# main.net
KiCad netlist of a schematic drawn in EAGLE
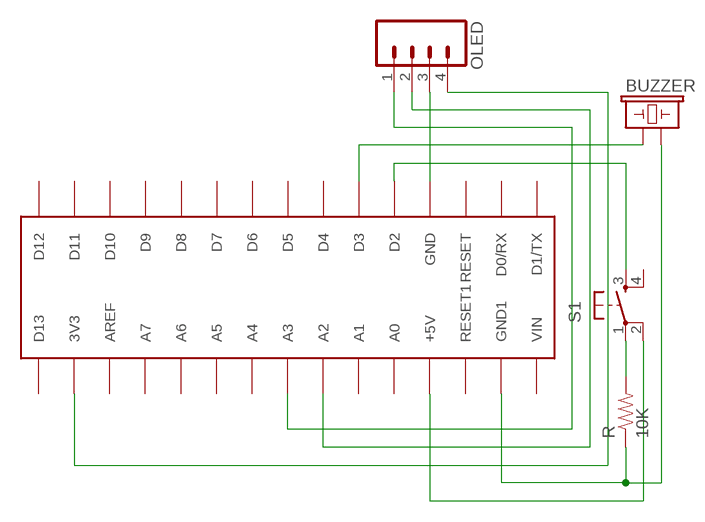
[diagram p0: schematic, sheet 1]

(export (version "E")
  (design (tool "Eeschema 10.0.6"))
  (components
    (comp (ref "BUZZER")
      (value "BUZZERPTH")
      (footprint "eagle-import:BUZZER-12MM")
      (libsource (lib "eagle-import") (part "BUZZERPTH"))
    )
    (comp (ref "NANO")
      (value "ARDUINONANO")
      (footprint "eagle-import:PDIP-32")
      (libsource (lib "eagle-import") (part "ARDUINONANO"))
    )
    (comp (ref "OLED")
      (value "M04LOCK_LONGPADS")
      (footprint "eagle-import:1X04_LOCK_LONGPADS")
      (libsource (lib "eagle-import") (part "M04LOCK_LONGPADS"))
    )
    (comp (ref "R")
      (value "10K")
      (footprint "eagle-import:AXIAL-0.3")
      (libsource (lib "eagle-import") (part "RESISTORAXIAL-0.3"))
    )
    (comp (ref "S1")
      (value "TAC_SWITCHPTH")
      (footprint "eagle-import:TACTILE-PTH")
      (libsource (lib "eagle-import") (part "TAC_SWITCHPTH"))
    )
  )
  (nets
    (net (code "1") (name "Net-(BUZZER-1)") (class "Default")
      (node (ref "BUZZER") (pin "+") (pinfunction "1_+") (pintype "passive"))
      (node (ref "NANO") (pin "D3") (pinfunction "D3_D3") (pintype "bidirectional"))
    )
    (net (code "2") (name "Net-(BUZZER-2)") (class "Default")
      (node (ref "BUZZER") (pin "-") (pinfunction "2_-") (pintype "passive"))
      (node (ref "NANO") (pin "GND1") (pinfunction "GND1_GND1") (pintype "bidirectional"))
      (node (ref "R") (pin "P$1") (pinfunction "1_P$1") (pintype "passive"))
    )
    (net (code "3") (name "Net-(NANO-Pad+5V)") (class "Default")
      (node (ref "NANO") (pin "+5V") (pinfunction "+5V_+5V") (pintype "bidirectional"))
      (node (ref "S1") (pin "2") (pinfunction "2_2") (pintype "passive"))
    )
    (net (code "4") (name "Net-(NANO-Pad3V3)") (class "Default")
      (node (ref "NANO") (pin "3V3") (pinfunction "3V3_3V3") (pintype "bidirectional"))
      (node (ref "OLED") (pin "4") (pinfunction "4_4") (pintype "passive"))
    )
    (net (code "5") (name "Net-(NANO-PadA2)") (class "Default")
      (node (ref "NANO") (pin "A2") (pinfunction "A2_A2") (pintype "bidirectional"))
      (node (ref "OLED") (pin "2") (pinfunction "2_2") (pintype "passive"))
    )
    (net (code "6") (name "Net-(NANO-PadA3)") (class "Default")
      (node (ref "NANO") (pin "A3") (pinfunction "A3_A3") (pintype "bidirectional"))
      (node (ref "OLED") (pin "1") (pinfunction "1_1") (pintype "passive"))
    )
    (net (code "7") (name "Net-(NANO-PadD2)") (class "Default")
      (node (ref "NANO") (pin "D2") (pinfunction "D2_D2") (pintype "bidirectional"))
      (node (ref "S1") (pin "3") (pinfunction "3_3") (pintype "passive"))
    )
    (net (code "8") (name "Net-(NANO-PadGND)") (class "Default")
      (node (ref "NANO") (pin "GND") (pinfunction "GND_GND") (pintype "bidirectional"))
      (node (ref "OLED") (pin "3") (pinfunction "3_3") (pintype "passive"))
    )
    (net (code "9") (name "Net-(R-2)") (class "Default")
      (node (ref "R") (pin "P$2") (pinfunction "2_P$2") (pintype "passive"))
      (node (ref "S1") (pin "1") (pinfunction "1_1") (pintype "passive"))
    )
    (net (code "10") (name "unconnected-(NANO-PadA0)") (class "Default")
      (node (ref "NANO") (pin "A0") (pinfunction "A0_A0") (pintype "bidirectional"))
    )
    (net (code "11") (name "unconnected-(NANO-PadA1)") (class "Default")
      (node (ref "NANO") (pin "A1") (pinfunction "A1_A1") (pintype "bidirectional"))
    )
    (net (code "12") (name "unconnected-(NANO-PadA4)") (class "Default")
      (node (ref "NANO") (pin "A4") (pinfunction "A4_A4") (pintype "bidirectional"))
    )
    (net (code "13") (name "unconnected-(NANO-PadA5)") (class "Default")
      (node (ref "NANO") (pin "A5") (pinfunction "A5_A5") (pintype "bidirectional"))
    )
    (net (code "14") (name "unconnected-(NANO-PadA6)") (class "Default")
      (node (ref "NANO") (pin "A6") (pinfunction "A6_A6") (pintype "bidirectional"))
    )
    (net (code "15") (name "unconnected-(NANO-PadA7)") (class "Default")
      (node (ref "NANO") (pin "A7") (pinfunction "A7_A7") (pintype "bidirectional"))
    )
    (net (code "16") (name "unconnected-(NANO-PadAREF)") (class "Default")
      (node (ref "NANO") (pin "AREF") (pinfunction "AREF_AREF") (pintype "bidirectional"))
    )
    (net (code "17") (name "unconnected-(NANO-PadD0{slash}RX)") (class "Default")
      (node (ref "NANO") (pin "D0/RX") (pinfunction "D0/RX_D0/RX") (pintype "bidirectional"))
    )
    (net (code "18") (name "unconnected-(NANO-PadD1{slash}TX)") (class "Default")
      (node (ref "NANO") (pin "D1/TX") (pinfunction "D1/TX_D1/TX") (pintype "bidirectional"))
    )
    (net (code "19") (name "unconnected-(NANO-PadD4)") (class "Default")
      (node (ref "NANO") (pin "D4") (pinfunction "D4_D4") (pintype "bidirectional"))
    )
    (net (code "20") (name "unconnected-(NANO-PadD5)") (class "Default")
      (node (ref "NANO") (pin "D5") (pinfunction "D5_D5") (pintype "bidirectional"))
    )
    (net (code "21") (name "unconnected-(NANO-PadD6)") (class "Default")
      (node (ref "NANO") (pin "D6") (pinfunction "D6_D6") (pintype "bidirectional"))
    )
    (net (code "22") (name "unconnected-(NANO-PadD7)") (class "Default")
      (node (ref "NANO") (pin "D7") (pinfunction "D7_D7") (pintype "bidirectional"))
    )
    (net (code "23") (name "unconnected-(NANO-PadD8)") (class "Default")
      (node (ref "NANO") (pin "D8") (pinfunction "D8_D8") (pintype "bidirectional"))
    )
    (net (code "24") (name "unconnected-(NANO-PadD9)") (class "Default")
      (node (ref "NANO") (pin "D9") (pinfunction "D9_D9") (pintype "bidirectional"))
    )
    (net (code "25") (name "unconnected-(NANO-PadD10)") (class "Default")
      (node (ref "NANO") (pin "D10") (pinfunction "D10_D10") (pintype "bidirectional"))
    )
    (net (code "26") (name "unconnected-(NANO-PadD11)") (class "Default")
      (node (ref "NANO") (pin "D11") (pinfunction "D11_D11") (pintype "bidirectional"))
    )
    (net (code "27") (name "unconnected-(NANO-PadD12)") (class "Default")
      (node (ref "NANO") (pin "D12") (pinfunction "D12_D12") (pintype "bidirectional"))
    )
    (net (code "28") (name "unconnected-(NANO-PadD13)") (class "Default")
      (node (ref "NANO") (pin "D13") (pinfunction "D13_D13") (pintype "bidirectional"))
    )
    (net (code "29") (name "unconnected-(NANO-PadRESET)") (class "Default")
      (node (ref "NANO") (pin "RESET") (pinfunction "RESET_RESET") (pintype "bidirectional"))
    )
    (net (code "30") (name "unconnected-(NANO-PadRESET1)") (class "Default")
      (node (ref "NANO") (pin "RESET1") (pinfunction "RESET1_RESET1") (pintype "bidirectional"))
    )
    (net (code "31") (name "unconnected-(NANO-PadVIN)") (class "Default")
      (node (ref "NANO") (pin "VIN") (pinfunction "VIN_VIN") (pintype "bidirectional"))
    )
    (net (code "32") (name "unconnected-(S1-Pad4)") (class "Default")
      (node (ref "S1") (pin "4") (pinfunction "4_4") (pintype "passive"))
    )
  )
)
